# Transmitter_Ckt.net
KiCad netlist of a schematic drawn in EAGLE
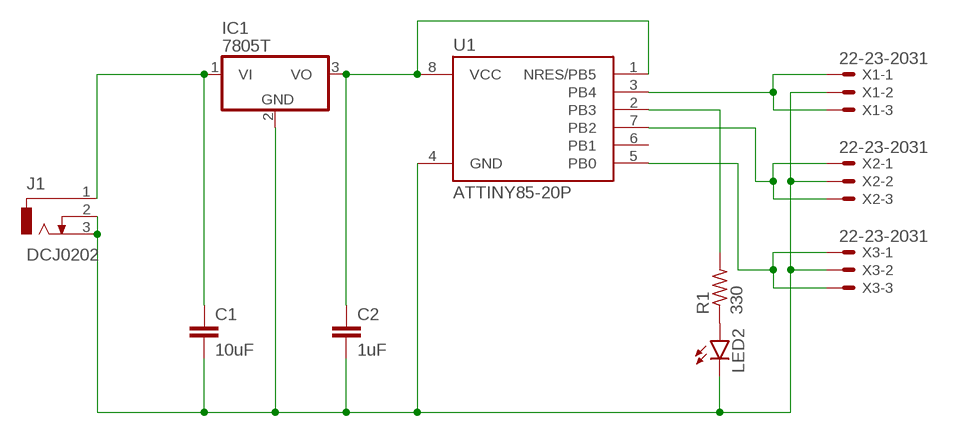
[diagram p0: schematic, sheet 1]

(export (version "E")
  (design (tool "Eeschema 10.0.6"))
  (components
    (comp (ref "C1")
      (value "10uF")
      (footprint "eagle-import:C0603")
      (libsource (lib "eagle-import") (part "C-EUC0603"))
    )
    (comp (ref "C2")
      (value "1uF")
      (footprint "eagle-import:C0603")
      (libsource (lib "eagle-import") (part "C-EUC0603"))
    )
    (comp (ref "IC1")
      (value "7805T")
      (footprint "eagle-import:TO220H")
      (libsource (lib "eagle-import") (part "78T05"))
    )
    (comp (ref "J1")
      (value "DCJ0202")
      (footprint "eagle-import:DCJ0202")
      (libsource (lib "eagle-import") (part "DCJ0202"))
    )
    (comp (ref "LED2")
      (value "LED3MM")
      (footprint "eagle-import:LED3MM")
      (libsource (lib "eagle-import") (part "LED3MM"))
    )
    (comp (ref "R1")
      (value "330")
      (footprint "eagle-import:R0603")
      (libsource (lib "eagle-import") (part "R-US_R0603"))
    )
    (comp (ref "U1")
      (value "ATTINY85-20P")
      (footprint "eagle-import:PDIP08_300MIL")
      (libsource (lib "eagle-import") (part "ATTINY85P-20"))
    )
    (comp (ref "X1")
      (value "22-23-2031")
      (footprint "eagle-import:22-23-2031")
      (fields (field (name "MF") "MOLEX"))
      (libsource (lib "eagle-import") (part "22-23-2031"))
    )
    (comp (ref "X2")
      (value "22-23-2031")
      (footprint "eagle-import:22-23-2031")
      (fields (field (name "MF") "MOLEX"))
      (libsource (lib "eagle-import") (part "22-23-2031"))
    )
    (comp (ref "X3")
      (value "22-23-2031")
      (footprint "eagle-import:22-23-2031")
      (fields (field (name "MF") "MOLEX"))
      (libsource (lib "eagle-import") (part "22-23-2031"))
    )
  )
  (nets
    (net (code "1") (name "Net-(IC1-GND)") (class "Default")
      (node (ref "C1") (pin "2") (pinfunction "2_2") (pintype "passive"))
      (node (ref "C2") (pin "2") (pinfunction "2_2") (pintype "passive"))
      (node (ref "IC1") (pin "2") (pinfunction "GND_2") (pintype "passive"))
      (node (ref "J1") (pin "2") (pinfunction "2_2") (pintype "passive"))
      (node (ref "J1") (pin "3") (pinfunction "3_3") (pintype "passive"))
      (node (ref "LED2") (pin "K") (pinfunction "C_K") (pintype "passive"))
      (node (ref "U1") (pin "4") (pinfunction "GND_4") (pintype "power_in"))
      (node (ref "X1") (pin "2") (pinfunction "S_2") (pintype "passive"))
      (node (ref "X2") (pin "2") (pinfunction "S_2") (pintype "passive"))
      (node (ref "X3") (pin "2") (pinfunction "S_2") (pintype "passive"))
    )
    (net (code "2") (name "Net-(IC1-VI)") (class "Default")
      (node (ref "C1") (pin "1") (pinfunction "1_1") (pintype "passive"))
      (node (ref "IC1") (pin "1") (pinfunction "VI_1") (pintype "input"))
      (node (ref "J1") (pin "1") (pinfunction "1_1") (pintype "passive"))
    )
    (net (code "3") (name "Net-(IC1-VO)") (class "Default")
      (node (ref "C2") (pin "1") (pinfunction "1_1") (pintype "passive"))
      (node (ref "IC1") (pin "3") (pinfunction "VO_3") (pintype "passive"))
      (node (ref "U1") (pin "1") (pinfunction "NRES/PB5_1") (pintype "bidirectional"))
      (node (ref "U1") (pin "8") (pinfunction "VCC_8") (pintype "power_in"))
    )
    (net (code "4") (name "Net-(LED2-PadA)") (class "Default")
      (node (ref "LED2") (pin "A") (pinfunction "A_A") (pintype "passive"))
      (node (ref "R1") (pin "1") (pinfunction "1_1") (pintype "passive"))
    )
    (net (code "5") (name "Net-(U1-PB0)") (class "Default")
      (node (ref "U1") (pin "5") (pinfunction "PB0_5") (pintype "bidirectional"))
      (node (ref "X3") (pin "1") (pinfunction "S_1") (pintype "passive"))
      (node (ref "X3") (pin "3") (pinfunction "S_3") (pintype "passive"))
    )
    (net (code "6") (name "Net-(U1-PB2)") (class "Default")
      (node (ref "U1") (pin "7") (pinfunction "PB2_7") (pintype "bidirectional"))
      (node (ref "X2") (pin "1") (pinfunction "S_1") (pintype "passive"))
      (node (ref "X2") (pin "3") (pinfunction "S_3") (pintype "passive"))
    )
    (net (code "7") (name "Net-(U1-PB3)") (class "Default")
      (node (ref "R1") (pin "2") (pinfunction "2_2") (pintype "passive"))
      (node (ref "U1") (pin "2") (pinfunction "PB3_2") (pintype "bidirectional"))
    )
    (net (code "8") (name "Net-(U1-PB4)") (class "Default")
      (node (ref "U1") (pin "3") (pinfunction "PB4_3") (pintype "bidirectional"))
      (node (ref "X1") (pin "1") (pinfunction "S_1") (pintype "passive"))
      (node (ref "X1") (pin "3") (pinfunction "S_3") (pintype "passive"))
    )
    (net (code "9") (name "unconnected-(U1-PB1-Pad6)") (class "Default")
      (node (ref "U1") (pin "6") (pinfunction "PB1_6") (pintype "bidirectional"))
    )
  )
)
